# RC_oscillator.net
KiCad netlist of a schematic drawn in EAGLE
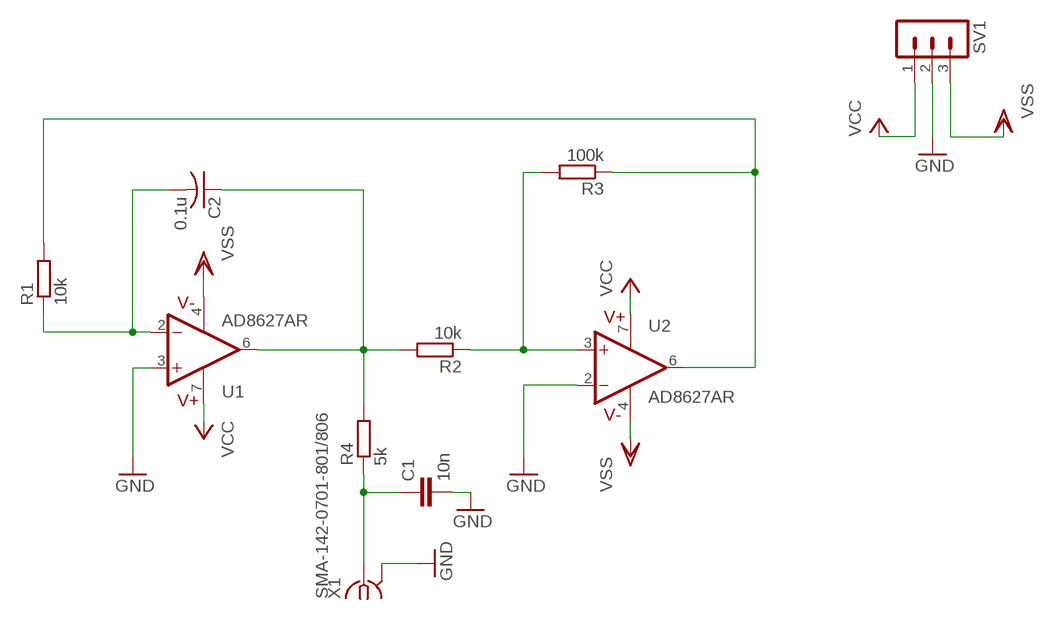
[diagram p0: schematic, sheet 1]

(export (version "E")
  (design (tool "Eeschema 10.0.6"))
  (components
    (comp (ref "C1")
      (value "10n")
      (footprint "eagle-import:C025-030X050")
      (libsource (lib "eagle-import") (part "C-EU025-030X050"))
    )
    (comp (ref "C2")
      (value "0.1u")
      (footprint "eagle-import:C0504")
      (libsource (lib "eagle-import") (part "C-USC0504"))
    )
    (comp (ref "R1")
      (value "10k")
      (footprint "eagle-import:R0805")
      (libsource (lib "eagle-import") (part "R-EU_R0805"))
    )
    (comp (ref "R2")
      (value "10k")
      (footprint "eagle-import:R0805")
      (libsource (lib "eagle-import") (part "R-EU_R0805"))
    )
    (comp (ref "R3")
      (value "100k")
      (footprint "eagle-import:R0805")
      (libsource (lib "eagle-import") (part "R-EU_R0805"))
    )
    (comp (ref "R4")
      (value "5k")
      (footprint "eagle-import:R0805")
      (libsource (lib "eagle-import") (part "R-EU_R0805"))
    )
    (comp (ref "SV1")
      (value "MA03-1")
      (footprint "eagle-import:MA03-1")
      (libsource (lib "eagle-import") (part "MA03-1"))
    )
    (comp (ref "U1")
      (value "AD8627AR")
      (footprint "eagle-import:SOIC8")
      (libsource (lib "eagle-import") (part "AD8627AR"))
    )
    (comp (ref "U2")
      (value "AD8627AR")
      (footprint "eagle-import:SOIC8")
      (libsource (lib "eagle-import") (part "AD8627AR"))
    )
    (comp (ref "X1")
      (value "SMA-142-0701-801/806")
      (footprint "eagle-import:J502-ND-142-0701-801_806")
      (fields (field (name "MF") "JOHNSON COMPONENTS") (field (name "MPN") "142-0701-801"))
      (libsource (lib "eagle-import") (part "SMA-142-0701-801/806"))
    )
  )
  (nets
    (net (code "1") (name "GND") (class "Default")
      (node (ref "C1") (pin "2") (pinfunction "2_2") (pintype "passive"))
      (node (ref "SV1") (pin "2") (pinfunction "2_2") (pintype "passive"))
      (node (ref "U1") (pin "3") (pinfunction "+IN_3") (pintype "input"))
      (node (ref "U2") (pin "2") (pinfunction "-IN_2") (pintype "input"))
      (node (ref "X1") (pin "G@1") (pinfunction "2_G@1") (pintype "passive"))
      (node (ref "X1") (pin "G@2") (pinfunction "2_G@2") (pintype "passive"))
      (node (ref "X1") (pin "G@3") (pinfunction "2_G@3") (pintype "passive"))
      (node (ref "X1") (pin "G@4") (pinfunction "2_G@4") (pintype "passive"))
    )
    (net (code "2") (name "Net-(C1-Pad1)") (class "Default")
      (node (ref "C1") (pin "1") (pinfunction "1_1") (pintype "passive"))
      (node (ref "R4") (pin "1") (pinfunction "1_1") (pintype "passive"))
      (node (ref "X1") (pin "1") (pinfunction "1_1") (pintype "passive"))
    )
    (net (code "3") (name "Net-(U1--IN)") (class "Default")
      (node (ref "C2") (pin "2") (pinfunction "2_2") (pintype "passive"))
      (node (ref "R1") (pin "1") (pinfunction "1_1") (pintype "passive"))
      (node (ref "U1") (pin "2") (pinfunction "-IN_2") (pintype "input"))
    )
    (net (code "4") (name "Net-(U1-OUT)") (class "Default")
      (node (ref "C2") (pin "1") (pinfunction "1_1") (pintype "passive"))
      (node (ref "R2") (pin "2") (pinfunction "2_2") (pintype "passive"))
      (node (ref "R4") (pin "2") (pinfunction "2_2") (pintype "passive"))
      (node (ref "U1") (pin "6") (pinfunction "OUT_6") (pintype "output"))
    )
    (net (code "5") (name "Net-(U2-+IN)") (class "Default")
      (node (ref "R2") (pin "1") (pinfunction "1_1") (pintype "passive"))
      (node (ref "R3") (pin "2") (pinfunction "2_2") (pintype "passive"))
      (node (ref "U2") (pin "3") (pinfunction "+IN_3") (pintype "input"))
    )
    (net (code "6") (name "Net-(U2-OUT)") (class "Default")
      (node (ref "R1") (pin "2") (pinfunction "2_2") (pintype "passive"))
      (node (ref "R3") (pin "1") (pinfunction "1_1") (pintype "passive"))
      (node (ref "U2") (pin "6") (pinfunction "OUT_6") (pintype "output"))
    )
    (net (code "7") (name "VCC") (class "Default")
      (node (ref "SV1") (pin "1") (pinfunction "1_1") (pintype "passive"))
      (node (ref "U1") (pin "7") (pinfunction "V+_7") (pintype "power_in"))
      (node (ref "U2") (pin "7") (pinfunction "V+_7") (pintype "power_in"))
    )
    (net (code "8") (name "VSS") (class "Default")
      (node (ref "SV1") (pin "3") (pinfunction "3_3") (pintype "passive"))
      (node (ref "U1") (pin "4") (pinfunction "V-_4") (pintype "power_in"))
      (node (ref "U2") (pin "4") (pinfunction "V-_4") (pintype "power_in"))
    )
  )
)
